# UVC_Controller.net
KiCad netlist of a schematic drawn in Altium Designer
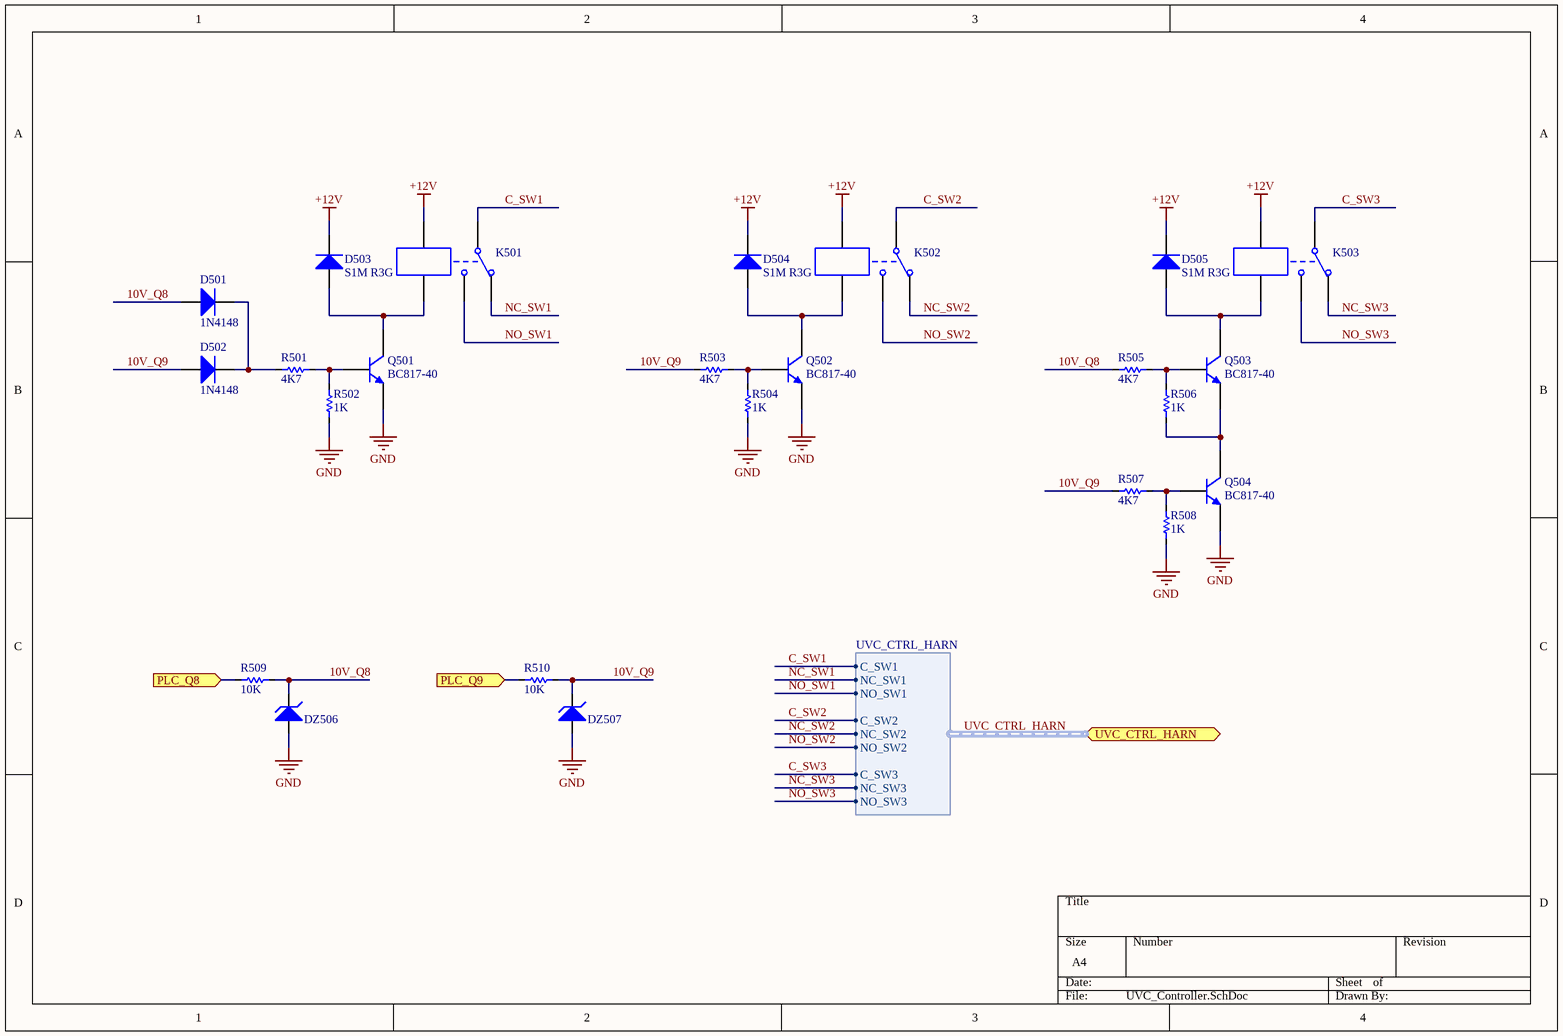
[diagram p0: UVC_Controller.SchDoc]

(export (version "E")
  (design (tool "Eeschema 10.0.6"))
  (components
    (comp (ref "D501")
      (value "Diodo Rectificador SMD")
      (footprint "SOD-80")
      (description "Diodo Rectificador")
      (fields (field (name "VALOR") "1N4148"))
      (libsource (lib "RUF-Dispositivos-Grales") (part "Diodo Rectificador SMD"))
    )
    (comp (ref "D502")
      (value "Diodo Rectificador SMD")
      (footprint "SOD-80")
      (description "Diodo Rectificador")
      (fields (field (name "VALOR") "1N4148"))
      (libsource (lib "RUF-Dispositivos-Grales") (part "Diodo Rectificador SMD"))
    )
    (comp (ref "D503")
      (value "Diodo Rectificador SMD")
      (footprint "DO-214")
      (description "Diodo Rectificador")
      (fields (field (name "VALOR") "S1M R3G"))
      (libsource (lib "RUF-Dispositivos-Grales") (part "Diodo Rectificador SMD"))
    )
    (comp (ref "D504")
      (value "Diodo Rectificador SMD")
      (footprint "DO-214")
      (description "Diodo Rectificador")
      (fields (field (name "VALOR") "S1M R3G"))
      (libsource (lib "RUF-Dispositivos-Grales") (part "Diodo Rectificador SMD"))
    )
    (comp (ref "D505")
      (value "Diodo Rectificador SMD")
      (footprint "DO-214")
      (description "Diodo Rectificador")
      (fields (field (name "VALOR") "S1M R3G"))
      (libsource (lib "RUF-Dispositivos-Grales") (part "Diodo Rectificador SMD"))
    )
    (comp (ref "DZ506")
      (value "Diodo Zenner SMD")
      (footprint "SOD-80")
      (description "Diodo zenner SMD")
      (libsource (lib "RUF-Dispositivos-Grales") (part "Diodo Zenner SMD"))
    )
    (comp (ref "DZ507")
      (value "Diodo Zenner SMD")
      (footprint "SOD-80")
      (description "Diodo zenner SMD")
      (libsource (lib "RUF-Dispositivos-Grales") (part "Diodo Zenner SMD"))
    )
    (comp (ref "K501")
      (value "Relay-SPDT")
      (footprint "JS1-5V-F")
      (description "Single-Pole Dual-Throw Relay")
      (fields (field (name "PUBLISHER") "Altium Limited"))
      (libsource (lib "Miscellaneous Devices") (part "Relay-SPDT"))
    )
    (comp (ref "K502")
      (value "Relay-SPDT")
      (footprint "JS1-5V-F")
      (description "Single-Pole Dual-Throw Relay")
      (fields (field (name "PUBLISHER") "Altium Limited"))
      (libsource (lib "Miscellaneous Devices") (part "Relay-SPDT"))
    )
    (comp (ref "K503")
      (value "Relay-SPDT")
      (footprint "JS1-5V-F")
      (description "Single-Pole Dual-Throw Relay")
      (fields (field (name "PUBLISHER") "Altium Limited"))
      (libsource (lib "Miscellaneous Devices") (part "Relay-SPDT"))
    )
    (comp (ref "Q501")
      (value "BC817-40")
      (footprint "SOT23_M")
      (description "NPN General-purpose Transistor")
      (fields (field (name "PUBLISHER") "Altium Limited"))
      (libsource (lib "Philips Discrete BJT - Low Power") (part "BC817-40"))
    )
    (comp (ref "Q502")
      (value "BC817-40")
      (footprint "SOT23_M")
      (description "NPN General-purpose Transistor")
      (fields (field (name "PUBLISHER") "Altium Limited"))
      (libsource (lib "Philips Discrete BJT - Low Power") (part "BC817-40"))
    )
    (comp (ref "Q503")
      (value "BC817-40")
      (footprint "SOT23_M")
      (description "NPN General-purpose Transistor")
      (fields (field (name "PUBLISHER") "Altium Limited"))
      (libsource (lib "Philips Discrete BJT - Low Power") (part "BC817-40"))
    )
    (comp (ref "Q504")
      (value "BC817-40")
      (footprint "SOT23_M")
      (description "NPN General-purpose Transistor")
      (fields (field (name "PUBLISHER") "Altium Limited"))
      (libsource (lib "Philips Discrete BJT - Low Power") (part "BC817-40"))
    )
    (comp (ref "R501")
      (value "Res SMD")
      (footprint "R0603")
      (description "Res Smd")
      (fields (field (name "VALOR") "4K7"))
      (libsource (lib "RUF-Dispositivos-Grales") (part "Res SMD"))
    )
    (comp (ref "R502")
      (value "Res SMD")
      (footprint "R0603")
      (description "Res Smd")
      (fields (field (name "VALOR") "1K"))
      (libsource (lib "RUF-Dispositivos-Grales") (part "Res SMD"))
    )
    (comp (ref "R503")
      (value "Res SMD")
      (footprint "R0603")
      (description "Res Smd")
      (fields (field (name "VALOR") "4K7"))
      (libsource (lib "RUF-Dispositivos-Grales") (part "Res SMD"))
    )
    (comp (ref "R504")
      (value "Res SMD")
      (footprint "R0603")
      (description "Res Smd")
      (fields (field (name "VALOR") "1K"))
      (libsource (lib "RUF-Dispositivos-Grales") (part "Res SMD"))
    )
    (comp (ref "R505")
      (value "Res SMD")
      (footprint "R0603")
      (description "Res Smd")
      (fields (field (name "VALOR") "4K7"))
      (libsource (lib "RUF-Dispositivos-Grales") (part "Res SMD"))
    )
    (comp (ref "R506")
      (value "Res SMD")
      (footprint "R0603")
      (description "Res Smd")
      (fields (field (name "VALOR") "1K"))
      (libsource (lib "RUF-Dispositivos-Grales") (part "Res SMD"))
    )
    (comp (ref "R507")
      (value "Res SMD")
      (footprint "R0603")
      (description "Res Smd")
      (fields (field (name "VALOR") "4K7"))
      (libsource (lib "RUF-Dispositivos-Grales") (part "Res SMD"))
    )
    (comp (ref "R508")
      (value "Res SMD")
      (footprint "R0603")
      (description "Res Smd")
      (fields (field (name "VALOR") "1K"))
      (libsource (lib "RUF-Dispositivos-Grales") (part "Res SMD"))
    )
    (comp (ref "R509")
      (value "Res SMD")
      (footprint "R0603")
      (description "Res Smd")
      (fields (field (name "VALOR") "10K"))
      (libsource (lib "RUF-Dispositivos-Grales") (part "Res SMD"))
    )
    (comp (ref "R510")
      (value "Res SMD")
      (footprint "R0603")
      (description "Res Smd")
      (fields (field (name "VALOR") "10K"))
      (libsource (lib "RUF-Dispositivos-Grales") (part "Res SMD"))
    )
  )
  (nets
    (net (code "2") (name "+12V") (class "Default")
      (node (ref "D503") (pin "2") (pinfunction "K_2") (pintype "passive"))
      (node (ref "D504") (pin "2") (pinfunction "K_2") (pintype "passive"))
      (node (ref "D505") (pin "2") (pinfunction "K_2") (pintype "passive"))
      (node (ref "K501") (pin "4") (pinfunction "4_4") (pintype "passive"))
      (node (ref "K502") (pin "4") (pinfunction "4_4") (pintype "passive"))
      (node (ref "K503") (pin "4") (pinfunction "4_4") (pintype "passive"))
    )
    (net (code "3") (name "/10V_Q8") (class "Default")
      (node (ref "D501") (pin "1") (pinfunction "A_1") (pintype "passive"))
      (node (ref "DZ506") (pin "2") (pinfunction "K_2") (pintype "passive"))
      (node (ref "R505") (pin "2") (pinfunction "2_2") (pintype "passive"))
      (node (ref "R509") (pin "2") (pinfunction "2_2") (pintype "passive"))
    )
    (net (code "4") (name "/10V_Q9") (class "Default")
      (node (ref "D502") (pin "1") (pinfunction "A_1") (pintype "passive"))
      (node (ref "DZ507") (pin "2") (pinfunction "K_2") (pintype "passive"))
      (node (ref "R503") (pin "2") (pinfunction "2_2") (pintype "passive"))
      (node (ref "R507") (pin "2") (pinfunction "2_2") (pintype "passive"))
      (node (ref "R510") (pin "2") (pinfunction "2_2") (pintype "passive"))
    )
    (net (code "5") (name "/C_SW1") (class "Default")
      (node (ref "K501") (pin "1") (pinfunction "1_1") (pintype "passive"))
    )
    (net (code "6") (name "/C_SW2") (class "Default")
      (node (ref "K502") (pin "1") (pinfunction "1_1") (pintype "passive"))
    )
    (net (code "7") (name "/C_SW3") (class "Default")
      (node (ref "K503") (pin "1") (pinfunction "1_1") (pintype "passive"))
    )
    (net (code "8") (name "/NC_SW1") (class "Default")
      (node (ref "K501") (pin "2") (pinfunction "2_2") (pintype "passive"))
    )
    (net (code "9") (name "/NC_SW2") (class "Default")
      (node (ref "K502") (pin "2") (pinfunction "2_2") (pintype "passive"))
    )
    (net (code "10") (name "/NC_SW3") (class "Default")
      (node (ref "K503") (pin "2") (pinfunction "2_2") (pintype "passive"))
    )
    (net (code "11") (name "/NO_SW1") (class "Default")
      (node (ref "K501") (pin "3") (pinfunction "3_3") (pintype "passive"))
    )
    (net (code "12") (name "/NO_SW2") (class "Default")
      (node (ref "K502") (pin "3") (pinfunction "3_3") (pintype "passive"))
    )
    (net (code "13") (name "/NO_SW3") (class "Default")
      (node (ref "K503") (pin "3") (pinfunction "3_3") (pintype "passive"))
    )
    (net (code "14") (name "/PLC_Q8") (class "Default")
      (node (ref "R509") (pin "1") (pinfunction "1_1") (pintype "passive"))
    )
    (net (code "15") (name "/PLC_Q9") (class "Default")
      (node (ref "R510") (pin "1") (pinfunction "1_1") (pintype "passive"))
    )
    (net (code "17") (name "GND") (class "Default")
      (node (ref "DZ506") (pin "1") (pinfunction "A_1") (pintype "passive"))
      (node (ref "DZ507") (pin "1") (pinfunction "A_1") (pintype "passive"))
      (node (ref "Q501") (pin "2") (pinfunction "E_2") (pintype "passive"))
      (node (ref "Q502") (pin "2") (pinfunction "E_2") (pintype "passive"))
      (node (ref "Q504") (pin "2") (pinfunction "E_2") (pintype "passive"))
      (node (ref "R502") (pin "2") (pinfunction "2_2") (pintype "passive"))
      (node (ref "R504") (pin "2") (pinfunction "2_2") (pintype "passive"))
      (node (ref "R508") (pin "2") (pinfunction "2_2") (pintype "passive"))
    )
    (net (code "18") (name "Net-(D501-K)") (class "Default")
      (node (ref "D501") (pin "2") (pinfunction "K_2") (pintype "passive"))
      (node (ref "D502") (pin "2") (pinfunction "K_2") (pintype "passive"))
      (node (ref "R501") (pin "2") (pinfunction "2_2") (pintype "passive"))
    )
    (net (code "19") (name "Net-(D503-A)") (class "Default")
      (node (ref "D503") (pin "1") (pinfunction "A_1") (pintype "passive"))
      (node (ref "K501") (pin "5") (pinfunction "5_5") (pintype "passive"))
      (node (ref "Q501") (pin "3") (pinfunction "C_3") (pintype "passive"))
    )
    (net (code "20") (name "Net-(D504-A)") (class "Default")
      (node (ref "D504") (pin "1") (pinfunction "A_1") (pintype "passive"))
      (node (ref "K502") (pin "5") (pinfunction "5_5") (pintype "passive"))
      (node (ref "Q502") (pin "3") (pinfunction "C_3") (pintype "passive"))
    )
    (net (code "21") (name "Net-(D505-A)") (class "Default")
      (node (ref "D505") (pin "1") (pinfunction "A_1") (pintype "passive"))
      (node (ref "K503") (pin "5") (pinfunction "5_5") (pintype "passive"))
      (node (ref "Q503") (pin "3") (pinfunction "C_3") (pintype "passive"))
    )
    (net (code "22") (name "Net-(Q501-B)") (class "Default")
      (node (ref "Q501") (pin "1") (pinfunction "B_1") (pintype "passive"))
      (node (ref "R501") (pin "1") (pinfunction "1_1") (pintype "passive"))
      (node (ref "R502") (pin "1") (pinfunction "1_1") (pintype "passive"))
    )
    (net (code "23") (name "Net-(Q502-B)") (class "Default")
      (node (ref "Q502") (pin "1") (pinfunction "B_1") (pintype "passive"))
      (node (ref "R503") (pin "1") (pinfunction "1_1") (pintype "passive"))
      (node (ref "R504") (pin "1") (pinfunction "1_1") (pintype "passive"))
    )
    (net (code "24") (name "Net-(Q503-B)") (class "Default")
      (node (ref "Q503") (pin "1") (pinfunction "B_1") (pintype "passive"))
      (node (ref "R505") (pin "1") (pinfunction "1_1") (pintype "passive"))
      (node (ref "R506") (pin "1") (pinfunction "1_1") (pintype "passive"))
    )
    (net (code "25") (name "Net-(Q503-E)") (class "Default")
      (node (ref "Q503") (pin "2") (pinfunction "E_2") (pintype "passive"))
      (node (ref "Q504") (pin "3") (pinfunction "C_3") (pintype "passive"))
      (node (ref "R506") (pin "2") (pinfunction "2_2") (pintype "passive"))
    )
    (net (code "26") (name "Net-(Q504-B)") (class "Default")
      (node (ref "Q504") (pin "1") (pinfunction "B_1") (pintype "passive"))
      (node (ref "R507") (pin "1") (pinfunction "1_1") (pintype "passive"))
      (node (ref "R508") (pin "1") (pinfunction "1_1") (pintype "passive"))
    )
  )
)
